# MAIN.net
KiCad netlist of a schematic drawn in Altium Designer
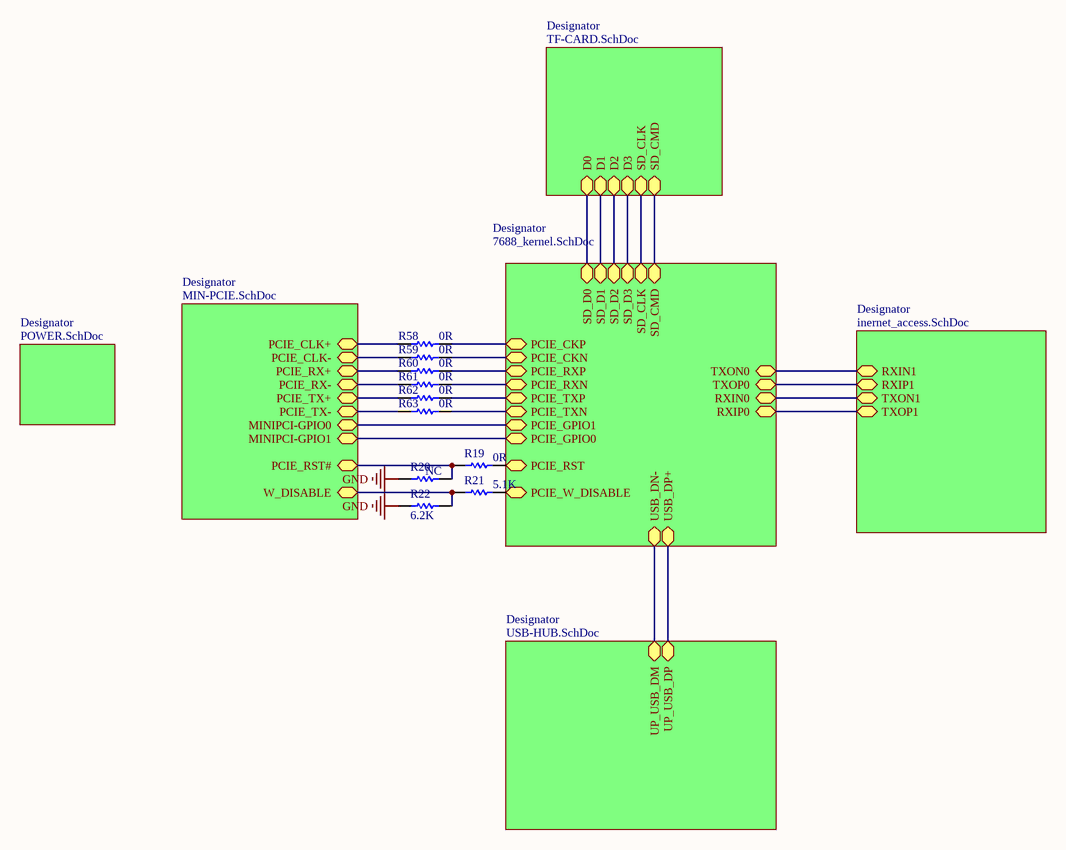
[diagram p0: MAIN.SchDoc]

(export (version "E")
  (design (tool "Eeschema 10.0.6"))
  (components
    (comp (ref "R19")
      (value "0R")
      (footprint "R0603N")
      (description "Semiconductor Resistor")
      (fields (field (name "PUBLISHER") "Altium Limited"))
      (libsource (lib "Miscellaneous Devices") (part "Res Semi"))
    )
    (comp (ref "R20")
      (value "NC")
      (footprint "R0603N")
      (description "Semiconductor Resistor")
      (fields (field (name "PUBLISHER") "Altium Limited"))
      (libsource (lib "Miscellaneous Devices") (part "Res Semi"))
    )
    (comp (ref "R21")
      (value "5.1K")
      (footprint "R0603N")
      (description "Semiconductor Resistor")
      (fields (field (name "PUBLISHER") "Altium Limited"))
      (libsource (lib "Miscellaneous Devices") (part "Res Semi"))
    )
    (comp (ref "R22")
      (value "6.2K")
      (footprint "R0603N")
      (description "Semiconductor Resistor")
      (fields (field (name "PUBLISHER") "Altium Limited"))
      (libsource (lib "Miscellaneous Devices") (part "Res Semi"))
    )
    (comp (ref "R58")
      (value "0R")
      (footprint "R0603N")
      (description "Semiconductor Resistor")
      (fields (field (name "PUBLISHER") "Altium Limited"))
      (libsource (lib "Miscellaneous Devices") (part "Res Semi"))
    )
    (comp (ref "R59")
      (value "0R")
      (footprint "R0603N")
      (description "Semiconductor Resistor")
      (fields (field (name "PUBLISHER") "Altium Limited"))
      (libsource (lib "Miscellaneous Devices") (part "Res Semi"))
    )
    (comp (ref "R60")
      (value "0R")
      (footprint "R0603N")
      (description "Semiconductor Resistor")
      (fields (field (name "PUBLISHER") "Altium Limited"))
      (libsource (lib "Miscellaneous Devices") (part "Res Semi"))
    )
    (comp (ref "R61")
      (value "0R")
      (footprint "R0603N")
      (description "Semiconductor Resistor")
      (fields (field (name "PUBLISHER") "Altium Limited"))
      (libsource (lib "Miscellaneous Devices") (part "Res Semi"))
    )
    (comp (ref "R62")
      (value "0R")
      (footprint "R0603N")
      (description "Semiconductor Resistor")
      (fields (field (name "PUBLISHER") "Altium Limited"))
      (libsource (lib "Miscellaneous Devices") (part "Res Semi"))
    )
    (comp (ref "R63")
      (value "0R")
      (footprint "R0603N")
      (description "Semiconductor Resistor")
      (fields (field (name "PUBLISHER") "Altium Limited"))
      (libsource (lib "Miscellaneous Devices") (part "Res Semi"))
    )
  )
  (nets
    (net (code "7") (name "/PCIE_CKN") (class "Default")
      (node (ref "R59") (pin "1") (pinfunction "1_1") (pintype "passive"))
    )
    (net (code "8") (name "/PCIE_CKP") (class "Default")
      (node (ref "R58") (pin "1") (pinfunction "1_1") (pintype "passive"))
    )
    (net (code "9") (name "/PCIE_CLK+") (class "Default")
      (node (ref "R58") (pin "2") (pinfunction "2_2") (pintype "passive"))
    )
    (net (code "10") (name "/PCIE_CLK-") (class "Default")
      (node (ref "R59") (pin "2") (pinfunction "2_2") (pintype "passive"))
    )
    (net (code "11") (name "/PCIE_RST") (class "Default")
      (node (ref "R19") (pin "2") (pinfunction "2_2") (pintype "passive"))
    )
    (net (code "12") (name "/PCIE_RST#") (class "Default")
      (node (ref "R19") (pin "1") (pinfunction "1_1") (pintype "passive"))
      (node (ref "R20") (pin "1") (pinfunction "1_1") (pintype "passive"))
    )
    (net (code "13") (name "/PCIE_RX+") (class "Default")
      (node (ref "R60") (pin "2") (pinfunction "2_2") (pintype "passive"))
    )
    (net (code "14") (name "/PCIE_RX-") (class "Default")
      (node (ref "R61") (pin "2") (pinfunction "2_2") (pintype "passive"))
    )
    (net (code "15") (name "/PCIE_RXN") (class "Default")
      (node (ref "R61") (pin "1") (pinfunction "1_1") (pintype "passive"))
    )
    (net (code "16") (name "/PCIE_RXP") (class "Default")
      (node (ref "R60") (pin "1") (pinfunction "1_1") (pintype "passive"))
    )
    (net (code "17") (name "/PCIE_TX+") (class "Default")
      (node (ref "R62") (pin "2") (pinfunction "2_2") (pintype "passive"))
    )
    (net (code "18") (name "/PCIE_TX-") (class "Default")
      (node (ref "R63") (pin "2") (pinfunction "2_2") (pintype "passive"))
    )
    (net (code "19") (name "/PCIE_TXN") (class "Default")
      (node (ref "R63") (pin "1") (pinfunction "1_1") (pintype "passive"))
    )
    (net (code "20") (name "/PCIE_TXP") (class "Default")
      (node (ref "R62") (pin "1") (pinfunction "1_1") (pintype "passive"))
    )
    (net (code "21") (name "/PCIE_W_DISABLE") (class "Default")
      (node (ref "R21") (pin "2") (pinfunction "2_2") (pintype "passive"))
    )
    (net (code "30") (name "/W_DISABLE") (class "Default")
      (node (ref "R21") (pin "1") (pinfunction "1_1") (pintype "passive"))
      (node (ref "R22") (pin "1") (pinfunction "1_1") (pintype "passive"))
    )
    (net (code "31") (name "GND") (class "Default")
      (node (ref "R20") (pin "2") (pinfunction "2_2") (pintype "passive"))
      (node (ref "R22") (pin "2") (pinfunction "2_2") (pintype "passive"))
    )
  )
)
